# breakout.net
KiCad netlist of a schematic drawn in EAGLE
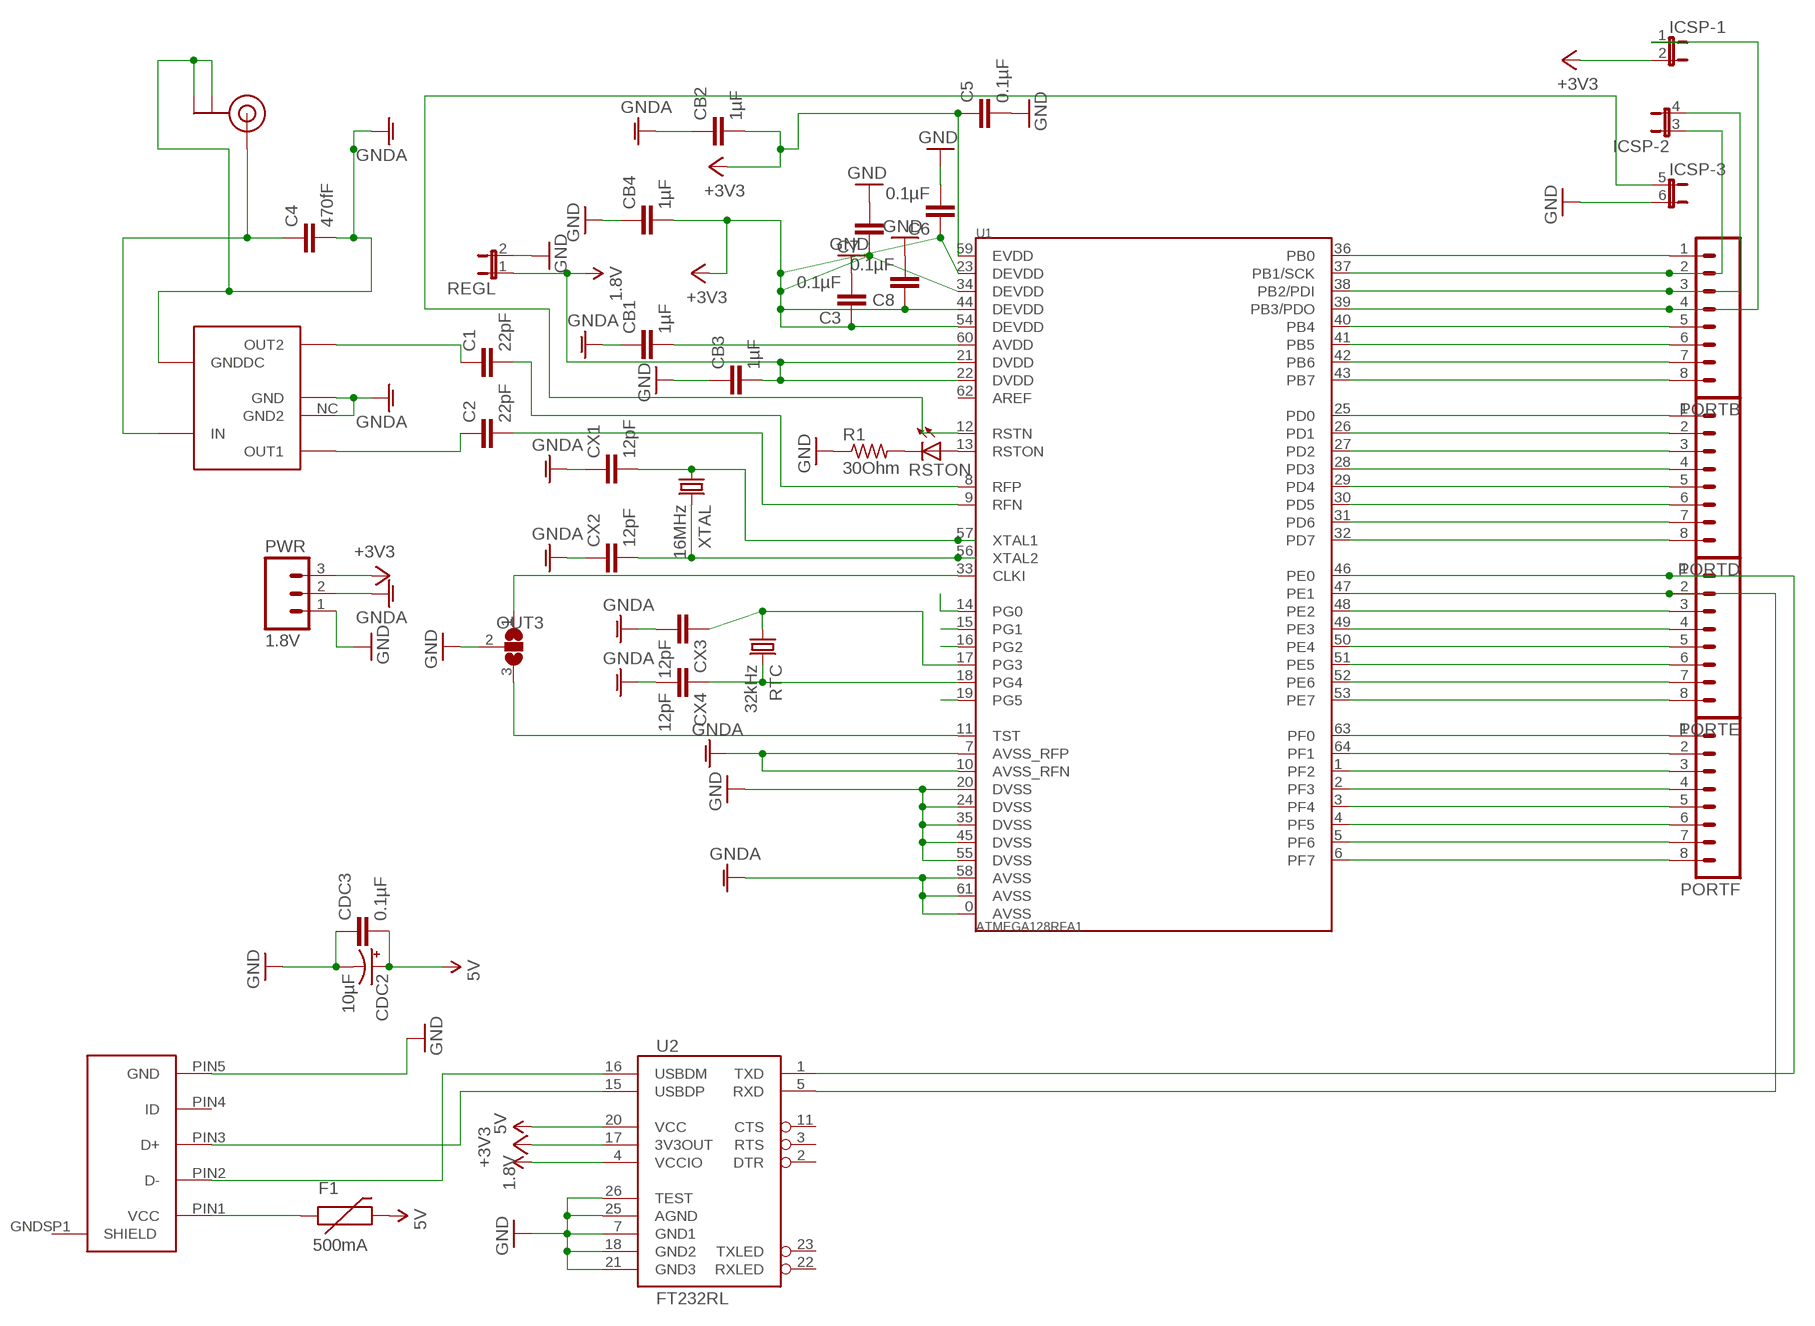
[diagram p0: schematic, sheet 1]

(export (version "E")
  (design (tool "Eeschema 10.0.6"))
  (components
    (comp (ref "B1")
      (value "2.4GHz")
      (footprint "eagle-import:WE-BAL")
      (libsource (lib "eagle-import") (part "WE-BAL"))
    )
    (comp (ref "C1")
      (value "22pF")
      (footprint "eagle-import:C0603")
      (libsource (lib "eagle-import") (part "C-EUC0603"))
    )
    (comp (ref "C2")
      (value "22pF")
      (footprint "eagle-import:C0603")
      (libsource (lib "eagle-import") (part "C-EUC0603"))
    )
    (comp (ref "C3")
      (value "0.1µF")
      (footprint "eagle-import:C0201")
      (libsource (lib "eagle-import") (part "C-EUC0201"))
    )
    (comp (ref "C4")
      (value "470fF")
      (footprint "eagle-import:C0402")
      (libsource (lib "eagle-import") (part "C-EUC0402"))
    )
    (comp (ref "C5")
      (value "0.1µF")
      (footprint "eagle-import:C0201")
      (libsource (lib "eagle-import") (part "C-EUC0201"))
    )
    (comp (ref "C6")
      (value "0.1µF")
      (footprint "eagle-import:C0201")
      (libsource (lib "eagle-import") (part "C-EUC0201"))
    )
    (comp (ref "C7")
      (value "C-EUC0201")
      (footprint "eagle-import:C0201")
      (libsource (lib "eagle-import") (part "C-EUC0201"))
    )
    (comp (ref "C8")
      (value "0.1µF")
      (footprint "eagle-import:C0201")
      (libsource (lib "eagle-import") (part "C-EUC0201"))
    )
    (comp (ref "CB1")
      (value "1µF")
      (footprint "eagle-import:C0603")
      (libsource (lib "eagle-import") (part "C-EUC0603"))
    )
    (comp (ref "CB2")
      (value "1µF")
      (footprint "eagle-import:C0603")
      (libsource (lib "eagle-import") (part "C-EUC0603"))
    )
    (comp (ref "CB3")
      (value "1µF")
      (footprint "eagle-import:C0603")
      (libsource (lib "eagle-import") (part "C-EUC0603"))
    )
    (comp (ref "CB4")
      (value "1µF")
      (footprint "eagle-import:C0603")
      (libsource (lib "eagle-import") (part "C-EUC0603"))
    )
    (comp (ref "CDC2")
      (value "10µF")
      (footprint "eagle-import:EIA3216")
      (libsource (lib "eagle-import") (part "CAP_POL1206"))
    )
    (comp (ref "CDC3")
      (value "0.1µF")
      (footprint "eagle-import:C0201")
      (libsource (lib "eagle-import") (part "C-EUC0201"))
    )
    (comp (ref "CX1")
      (value "12pF")
      (footprint "eagle-import:C0603")
      (libsource (lib "eagle-import") (part "C-EUC0603"))
    )
    (comp (ref "CX2")
      (value "12pF")
      (footprint "eagle-import:C0603")
      (libsource (lib "eagle-import") (part "C-EUC0603"))
    )
    (comp (ref "CX3")
      (value "12pF")
      (footprint "eagle-import:C0603")
      (libsource (lib "eagle-import") (part "C-EUC0603"))
    )
    (comp (ref "CX4")
      (value "12pF")
      (footprint "eagle-import:C0603")
      (libsource (lib "eagle-import") (part "C-EUC0603"))
    )
    (comp (ref "F1")
      (value "500mA")
      (footprint "eagle-import:0603")
      (libsource (lib "eagle-import") (part "PTC0603"))
    )
    (comp (ref "ICSP")
      (value "JP3QE")
      (footprint "eagle-import:JP3Q")
      (libsource (lib "eagle-import") (part "JP3QE"))
    )
    (comp (ref "JP1")
      (value "USBMICROB")
      (footprint "eagle-import:MICROB")
      (libsource (lib "eagle-import") (part "USBMICROB"))
    )
    (comp (ref "OUT3")
      (value "SOLDERJUMPERNO")
      (footprint "eagle-import:SJ_2")
      (libsource (lib "eagle-import") (part "SJ2W"))
    )
    (comp (ref "PORTB")
      (value "M081X08")
      (footprint "eagle-import:1X08")
      (libsource (lib "eagle-import") (part "M081X08"))
    )
    (comp (ref "PORTD")
      (value "M081X08")
      (footprint "eagle-import:1X08")
      (libsource (lib "eagle-import") (part "M081X08"))
    )
    (comp (ref "PORTE")
      (value "M081X08")
      (footprint "eagle-import:1X08")
      (libsource (lib "eagle-import") (part "M081X08"))
    )
    (comp (ref "PORTF")
      (value "M081X08")
      (footprint "eagle-import:1X08")
      (libsource (lib "eagle-import") (part "M081X08"))
    )
    (comp (ref "PWR")
      (value "1.8V")
      (footprint "eagle-import:1X03")
      (libsource (lib "eagle-import") (part "M03PTH"))
    )
    (comp (ref "R1")
      (value "30Ohm")
      (footprint "eagle-import:R0603")
      (libsource (lib "eagle-import") (part "R-US_R0603"))
    )
    (comp (ref "REGL")
      (value "JP1E")
      (footprint "eagle-import:JP1")
      (libsource (lib "eagle-import") (part "JP1E"))
    )
    (comp (ref "RSTON")
      (value "LEDCHIPLED_0603")
      (footprint "eagle-import:CHIPLED_0603")
      (libsource (lib "eagle-import") (part "LEDCHIPLED_0603"))
    )
    (comp (ref "RTC")
      (value "32kHz")
      (footprint "eagle-import:TC26H")
      (libsource (lib "eagle-import") (part "CRYSTALTC26H"))
    )
    (comp (ref "U$6")
      (value "U.FL")
      (footprint "eagle-import:U.FL")
      (libsource (lib "eagle-import") (part "U.FL"))
    )
    (comp (ref "U1")
      (value "ATMEGA128RFA1")
      (footprint "eagle-import:QFN-64")
      (libsource (lib "eagle-import") (part "ATMEGA128RFA1"))
    )
    (comp (ref "U2")
      (value "FT232RL")
      (footprint "eagle-import:SSOP28DB")
      (libsource (lib "eagle-import") (part "FT232RL-BASICSSOP"))
    )
    (comp (ref "XTAL")
      (value "16MHz")
      (footprint "eagle-import:HC49UP")
      (libsource (lib "eagle-import") (part "CRYSTALHC49UP"))
    )
  )
  (nets
    (net (code "1") (name "+3V3") (class "Default")
      (node (ref "C3") (pin "1") (pinfunction "1_1") (pintype "passive"))
      (node (ref "C5") (pin "1") (pinfunction "1_1") (pintype "passive"))
      (node (ref "C6") (pin "1") (pinfunction "1_1") (pintype "passive"))
      (node (ref "C7") (pin "1") (pinfunction "1_1") (pintype "passive"))
      (node (ref "C8") (pin "1") (pinfunction "1_1") (pintype "passive"))
      (node (ref "CB2") (pin "2") (pinfunction "2_2") (pintype "passive"))
      (node (ref "CB4") (pin "2") (pinfunction "2_2") (pintype "passive"))
      (node (ref "ICSP") (pin "2") (pinfunction "2_2") (pintype "passive"))
      (node (ref "PWR") (pin "3") (pinfunction "3_3") (pintype "passive"))
      (node (ref "U1") (pin "23") (pinfunction "DEVDD_23") (pintype "bidirectional"))
      (node (ref "U1") (pin "34") (pinfunction "DEVDD_34") (pintype "bidirectional"))
      (node (ref "U1") (pin "44") (pinfunction "DEVDD_44") (pintype "bidirectional"))
      (node (ref "U1") (pin "54") (pinfunction "DEVDD_54") (pintype "bidirectional"))
      (node (ref "U1") (pin "59") (pinfunction "EVDD_59") (pintype "bidirectional"))
      (node (ref "U2") (pin "17") (pinfunction "3V3OUT_17") (pintype "output"))
    )
    (net (code "2") (name "/SHIELD") (class "Default")
      (node (ref "JP1") (pin "GNDSP1") (pinfunction "SHIELD_GNDSP1") (pintype "power_in"))
    )
    (net (code "3") (name "1.8V") (class "Default")
      (node (ref "CB3") (pin "2") (pinfunction "2_2") (pintype "passive"))
      (node (ref "REGL") (pin "1") (pinfunction "1_1") (pintype "passive"))
      (node (ref "U1") (pin "21") (pinfunction "DVDD_21") (pintype "bidirectional"))
      (node (ref "U1") (pin "22") (pinfunction "DVDD_22") (pintype "bidirectional"))
      (node (ref "U2") (pin "4") (pinfunction "VCCIO_4") (pintype "power_in"))
    )
    (net (code "4") (name "5V") (class "Default")
      (node (ref "CDC2") (pin "A") (pinfunction "+_A") (pintype "passive"))
      (node (ref "CDC3") (pin "2") (pinfunction "2_2") (pintype "passive"))
      (node (ref "F1") (pin "2") (pinfunction "2_2") (pintype "bidirectional"))
      (node (ref "U2") (pin "20") (pinfunction "VCC_20") (pintype "power_in"))
    )
    (net (code "5") (name "GND") (class "Default")
      (node (ref "C3") (pin "2") (pinfunction "2_2") (pintype "passive"))
      (node (ref "C5") (pin "2") (pinfunction "2_2") (pintype "passive"))
      (node (ref "C6") (pin "2") (pinfunction "2_2") (pintype "passive"))
      (node (ref "C7") (pin "2") (pinfunction "2_2") (pintype "passive"))
      (node (ref "C8") (pin "2") (pinfunction "2_2") (pintype "passive"))
      (node (ref "CB3") (pin "1") (pinfunction "1_1") (pintype "passive"))
      (node (ref "CB4") (pin "1") (pinfunction "1_1") (pintype "passive"))
      (node (ref "CDC2") (pin "C") (pinfunction "-_C") (pintype "passive"))
      (node (ref "CDC3") (pin "1") (pinfunction "1_1") (pintype "passive"))
      (node (ref "ICSP") (pin "6") (pinfunction "2_6") (pintype "passive"))
      (node (ref "JP1") (pin "PIN5") (pinfunction "GND_PIN5") (pintype "power_in"))
      (node (ref "OUT3") (pin "2") (pinfunction "2_2") (pintype "passive"))
      (node (ref "PWR") (pin "1") (pinfunction "1_1") (pintype "passive"))
      (node (ref "R1") (pin "1") (pinfunction "1_1") (pintype "passive"))
      (node (ref "REGL") (pin "2") (pinfunction "2_2") (pintype "passive"))
      (node (ref "U1") (pin "20") (pinfunction "DVSS_20") (pintype "bidirectional"))
      (node (ref "U1") (pin "24") (pinfunction "DVSS_24") (pintype "bidirectional"))
      (node (ref "U1") (pin "35") (pinfunction "DVSS_35") (pintype "bidirectional"))
      (node (ref "U1") (pin "45") (pinfunction "DVSS_45") (pintype "bidirectional"))
      (node (ref "U1") (pin "55") (pinfunction "DVSS_55") (pintype "bidirectional"))
      (node (ref "U2") (pin "18") (pinfunction "GND2_18") (pintype "power_in"))
      (node (ref "U2") (pin "21") (pinfunction "GND3_21") (pintype "power_in"))
      (node (ref "U2") (pin "25") (pinfunction "AGND_25") (pintype "power_in"))
      (node (ref "U2") (pin "26") (pinfunction "TEST_26") (pintype "input"))
      (node (ref "U2") (pin "7") (pinfunction "GND1_7") (pintype "power_in"))
    )
    (net (code "6") (name "GNDA") (class "Default")
      (node (ref "B1") (pin "GND") (pinfunction "GND_GND") (pintype "bidirectional"))
      (node (ref "B1") (pin "GNDDC") (pinfunction "GNDDC_GNDDC") (pintype "bidirectional"))
      (node (ref "B1") (pin "NC") (pinfunction "GND2_NC") (pintype "bidirectional"))
      (node (ref "C4") (pin "2") (pinfunction "2_2") (pintype "passive"))
      (node (ref "CB1") (pin "1") (pinfunction "1_1") (pintype "passive"))
      (node (ref "CB2") (pin "1") (pinfunction "1_1") (pintype "passive"))
      (node (ref "CX1") (pin "1") (pinfunction "1_1") (pintype "passive"))
      (node (ref "CX2") (pin "1") (pinfunction "1_1") (pintype "passive"))
      (node (ref "CX3") (pin "2") (pinfunction "2_2") (pintype "passive"))
      (node (ref "CX4") (pin "2") (pinfunction "2_2") (pintype "passive"))
      (node (ref "PWR") (pin "2") (pinfunction "2_2") (pintype "passive"))
      (node (ref "U$6") (pin "P$1") (pinfunction "GND_P$1") (pintype "bidirectional"))
      (node (ref "U$6") (pin "P$2") (pinfunction "GND_P$2") (pintype "bidirectional"))
      (node (ref "U1") (pin "0") (pinfunction "AVSS_0") (pintype "bidirectional"))
      (node (ref "U1") (pin "10") (pinfunction "AVSS_RFN_10") (pintype "bidirectional"))
      (node (ref "U1") (pin "58") (pinfunction "AVSS_58") (pintype "bidirectional"))
      (node (ref "U1") (pin "61") (pinfunction "AVSS_61") (pintype "bidirectional"))
      (node (ref "U1") (pin "7") (pinfunction "AVSS_RFP_7") (pintype "bidirectional"))
    )
    (net (code "7") (name "Net-(B1-PadOUT1)") (class "Default")
      (node (ref "B1") (pin "OUT1") (pinfunction "OUT1_OUT1") (pintype "bidirectional"))
      (node (ref "C2") (pin "1") (pinfunction "1_1") (pintype "passive"))
    )
    (net (code "8") (name "Net-(B1-PadOUT2)") (class "Default")
      (node (ref "B1") (pin "OUT2") (pinfunction "OUT2_OUT2") (pintype "bidirectional"))
      (node (ref "C1") (pin "1") (pinfunction "1_1") (pintype "passive"))
    )
    (net (code "9") (name "Net-(ICSPB-1)") (class "Default")
      (node (ref "ICSP") (pin "3") (pinfunction "1_3") (pintype "passive"))
      (node (ref "PORTB") (pin "2") (pinfunction "2_2") (pintype "passive"))
      (node (ref "U1") (pin "37") (pinfunction "PB1/SCK_37") (pintype "bidirectional"))
    )
    (net (code "10") (name "Net-(ICSPB-2)") (class "Default")
      (node (ref "ICSP") (pin "4") (pinfunction "2_4") (pintype "passive"))
      (node (ref "PORTB") (pin "3") (pinfunction "3_3") (pintype "passive"))
      (node (ref "U1") (pin "38") (pinfunction "PB2/PDI_38") (pintype "bidirectional"))
    )
    (net (code "11") (name "Net-(ICSPC-1)") (class "Default")
      (node (ref "ICSP") (pin "5") (pinfunction "1_5") (pintype "passive"))
      (node (ref "U1") (pin "12") (pinfunction "RSTN_12") (pintype "bidirectional"))
    )
    (net (code "12") (name "Net-(JP1-D+)") (class "Default")
      (node (ref "JP1") (pin "PIN3") (pinfunction "D+_PIN3") (pintype "bidirectional"))
      (node (ref "U2") (pin "15") (pinfunction "USBDP_15") (pintype "bidirectional"))
    )
    (net (code "13") (name "Net-(JP1-D-)") (class "Default")
      (node (ref "JP1") (pin "PIN2") (pinfunction "D-_PIN2") (pintype "bidirectional"))
      (node (ref "U2") (pin "16") (pinfunction "USBDM_16") (pintype "bidirectional"))
    )
    (net (code "14") (name "Net-(JP1-VCC)") (class "Default")
      (node (ref "F1") (pin "1") (pinfunction "1_1") (pintype "bidirectional"))
      (node (ref "JP1") (pin "PIN1") (pinfunction "VCC_PIN1") (pintype "power_in"))
    )
    (net (code "15") (name "Net-(R1-Pad2)") (class "Default")
      (node (ref "R1") (pin "2") (pinfunction "2_2") (pintype "passive"))
      (node (ref "RSTON") (pin "C") (pinfunction "C_C") (pintype "passive"))
    )
    (net (code "16") (name "Net-(U$6-SIGNAL)") (class "Default")
      (node (ref "B1") (pin "IN") (pinfunction "IN_IN") (pintype "bidirectional"))
      (node (ref "C4") (pin "1") (pinfunction "1_1") (pintype "passive"))
      (node (ref "U$6") (pin "P$3") (pinfunction "SIGNAL_P$3") (pintype "bidirectional"))
    )
    (net (code "17") (name "Net-(U1-AVDD)") (class "Default")
      (node (ref "CB1") (pin "2") (pinfunction "2_2") (pintype "passive"))
      (node (ref "U1") (pin "60") (pinfunction "AVDD_60") (pintype "bidirectional"))
    )
    (net (code "18") (name "Net-(U1-CLKI)") (class "Default")
      (node (ref "OUT3") (pin "1") (pinfunction "1_1") (pintype "passive"))
      (node (ref "U1") (pin "33") (pinfunction "CLKI_33") (pintype "bidirectional"))
    )
    (net (code "19") (name "Net-(U1-PB0)") (class "Default")
      (node (ref "PORTB") (pin "1") (pinfunction "1_1") (pintype "passive"))
      (node (ref "U1") (pin "36") (pinfunction "PB0_36") (pintype "bidirectional"))
    )
    (net (code "20") (name "Net-(U1-PB3{slash}PDO)") (class "Default")
      (node (ref "ICSP") (pin "1") (pinfunction "1_1") (pintype "passive"))
      (node (ref "PORTB") (pin "4") (pinfunction "4_4") (pintype "passive"))
      (node (ref "U1") (pin "39") (pinfunction "PB3/PDO_39") (pintype "bidirectional"))
    )
    (net (code "21") (name "Net-(U1-PB4)") (class "Default")
      (node (ref "PORTB") (pin "5") (pinfunction "5_5") (pintype "passive"))
      (node (ref "U1") (pin "40") (pinfunction "PB4_40") (pintype "bidirectional"))
    )
    (net (code "22") (name "Net-(U1-PB5)") (class "Default")
      (node (ref "PORTB") (pin "6") (pinfunction "6_6") (pintype "passive"))
      (node (ref "U1") (pin "41") (pinfunction "PB5_41") (pintype "bidirectional"))
    )
    (net (code "23") (name "Net-(U1-PB6)") (class "Default")
      (node (ref "PORTB") (pin "7") (pinfunction "7_7") (pintype "passive"))
      (node (ref "U1") (pin "42") (pinfunction "PB6_42") (pintype "bidirectional"))
    )
    (net (code "24") (name "Net-(U1-PB7)") (class "Default")
      (node (ref "PORTB") (pin "8") (pinfunction "8_8") (pintype "passive"))
      (node (ref "U1") (pin "43") (pinfunction "PB7_43") (pintype "bidirectional"))
    )
    (net (code "25") (name "Net-(U1-PD0)") (class "Default")
      (node (ref "PORTD") (pin "1") (pinfunction "1_1") (pintype "passive"))
      (node (ref "U1") (pin "25") (pinfunction "PD0_25") (pintype "bidirectional"))
    )
    (net (code "26") (name "Net-(U1-PD1)") (class "Default")
      (node (ref "PORTD") (pin "2") (pinfunction "2_2") (pintype "passive"))
      (node (ref "U1") (pin "26") (pinfunction "PD1_26") (pintype "bidirectional"))
    )
    (net (code "27") (name "Net-(U1-PD2)") (class "Default")
      (node (ref "PORTD") (pin "3") (pinfunction "3_3") (pintype "passive"))
      (node (ref "U1") (pin "27") (pinfunction "PD2_27") (pintype "bidirectional"))
    )
    (net (code "28") (name "Net-(U1-PD3)") (class "Default")
      (node (ref "PORTD") (pin "4") (pinfunction "4_4") (pintype "passive"))
      (node (ref "U1") (pin "28") (pinfunction "PD3_28") (pintype "bidirectional"))
    )
    (net (code "29") (name "Net-(U1-PD4)") (class "Default")
      (node (ref "PORTD") (pin "5") (pinfunction "5_5") (pintype "passive"))
      (node (ref "U1") (pin "29") (pinfunction "PD4_29") (pintype "bidirectional"))
    )
    (net (code "30") (name "Net-(U1-PD5)") (class "Default")
      (node (ref "PORTD") (pin "6") (pinfunction "6_6") (pintype "passive"))
      (node (ref "U1") (pin "30") (pinfunction "PD5_30") (pintype "bidirectional"))
    )
    (net (code "31") (name "Net-(U1-PD6)") (class "Default")
      (node (ref "PORTD") (pin "7") (pinfunction "7_7") (pintype "passive"))
      (node (ref "U1") (pin "31") (pinfunction "PD6_31") (pintype "bidirectional"))
    )
    (net (code "32") (name "Net-(U1-PD7)") (class "Default")
      (node (ref "PORTD") (pin "8") (pinfunction "8_8") (pintype "passive"))
      (node (ref "U1") (pin "32") (pinfunction "PD7_32") (pintype "bidirectional"))
    )
    (net (code "33") (name "Net-(U1-PE0)") (class "Default")
      (node (ref "PORTE") (pin "1") (pinfunction "1_1") (pintype "passive"))
      (node (ref "U1") (pin "46") (pinfunction "PE0_46") (pintype "bidirectional"))
      (node (ref "U2") (pin "1") (pinfunction "TXD_1") (pintype "output"))
    )
    (net (code "34") (name "Net-(U1-PE1)") (class "Default")
      (node (ref "PORTE") (pin "2") (pinfunction "2_2") (pintype "passive"))
      (node (ref "U1") (pin "47") (pinfunction "PE1_47") (pintype "bidirectional"))
      (node (ref "U2") (pin "5") (pinfunction "RXD_5") (pintype "input"))
    )
    (net (code "35") (name "Net-(U1-PE2)") (class "Default")
      (node (ref "PORTE") (pin "3") (pinfunction "3_3") (pintype "passive"))
      (node (ref "U1") (pin "48") (pinfunction "PE2_48") (pintype "bidirectional"))
    )
    (net (code "36") (name "Net-(U1-PE3)") (class "Default")
      (node (ref "PORTE") (pin "4") (pinfunction "4_4") (pintype "passive"))
      (node (ref "U1") (pin "49") (pinfunction "PE3_49") (pintype "bidirectional"))
    )
    (net (code "37") (name "Net-(U1-PE4)") (class "Default")
      (node (ref "PORTE") (pin "5") (pinfunction "5_5") (pintype "passive"))
      (node (ref "U1") (pin "50") (pinfunction "PE4_50") (pintype "bidirectional"))
    )
    (net (code "38") (name "Net-(U1-PE5)") (class "Default")
      (node (ref "PORTE") (pin "6") (pinfunction "6_6") (pintype "passive"))
      (node (ref "U1") (pin "51") (pinfunction "PE5_51") (pintype "bidirectional"))
    )
    (net (code "39") (name "Net-(U1-PE6)") (class "Default")
      (node (ref "PORTE") (pin "7") (pinfunction "7_7") (pintype "passive"))
      (node (ref "U1") (pin "52") (pinfunction "PE6_52") (pintype "bidirectional"))
    )
    (net (code "40") (name "Net-(U1-PE7)") (class "Default")
      (node (ref "PORTE") (pin "8") (pinfunction "8_8") (pintype "passive"))
      (node (ref "U1") (pin "53") (pinfunction "PE7_53") (pintype "bidirectional"))
    )
    (net (code "41") (name "Net-(U1-PF0)") (class "Default")
      (node (ref "PORTF") (pin "1") (pinfunction "1_1") (pintype "passive"))
      (node (ref "U1") (pin "63") (pinfunction "PF0_63") (pintype "bidirectional"))
    )
    (net (code "42") (name "Net-(U1-PF1)") (class "Default")
      (node (ref "PORTF") (pin "2") (pinfunction "2_2") (pintype "passive"))
      (node (ref "U1") (pin "64") (pinfunction "PF1_64") (pintype "bidirectional"))
    )
    (net (code "43") (name "Net-(U1-PF2)") (class "Default")
      (node (ref "PORTF") (pin "3") (pinfunction "3_3") (pintype "passive"))
      (node (ref "U1") (pin "1") (pinfunction "PF2_1") (pintype "bidirectional"))
    )
    (net (code "44") (name "Net-(U1-PF3)") (class "Default")
      (node (ref "PORTF") (pin "4") (pinfunction "4_4") (pintype "passive"))
      (node (ref "U1") (pin "2") (pinfunction "PF3_2") (pintype "bidirectional"))
    )
    (net (code "45") (name "Net-(U1-PF4)") (class "Default")
      (node (ref "PORTF") (pin "5") (pinfunction "5_5") (pintype "passive"))
      (node (ref "U1") (pin "3") (pinfunction "PF4_3") (pintype "bidirectional"))
    )
    (net (code "46") (name "Net-(U1-PF5)") (class "Default")
      (node (ref "PORTF") (pin "6") (pinfunction "6_6") (pintype "passive"))
      (node (ref "U1") (pin "4") (pinfunction "PF5_4") (pintype "bidirectional"))
    )
    (net (code "47") (name "Net-(U1-PF6)") (class "Default")
      (node (ref "PORTF") (pin "7") (pinfunction "7_7") (pintype "passive"))
      (node (ref "U1") (pin "5") (pinfunction "PF6_5") (pintype "bidirectional"))
    )
    (net (code "48") (name "Net-(U1-PF7)") (class "Default")
      (node (ref "PORTF") (pin "8") (pinfunction "8_8") (pintype "passive"))
      (node (ref "U1") (pin "6") (pinfunction "PF7_6") (pintype "bidirectional"))
    )
    (net (code "49") (name "Net-(U1-PG3)") (class "Default")
      (node (ref "CX3") (pin "1") (pinfunction "1_1") (pintype "passive"))
      (node (ref "RTC") (pin "1") (pinfunction "1_1") (pintype "passive"))
      (node (ref "U1") (pin "17") (pinfunction "PG3_17") (pintype "bidirectional"))
    )
    (net (code "50") (name "Net-(U1-PG4)") (class "Default")
      (node (ref "CX4") (pin "1") (pinfunction "1_1") (pintype "passive"))
      (node (ref "RTC") (pin "2") (pinfunction "2_2") (pintype "passive"))
      (node (ref "U1") (pin "18") (pinfunction "PG4_18") (pintype "bidirectional"))
    )
    (net (code "51") (name "Net-(U1-RFN)") (class "Default")
      (node (ref "C2") (pin "2") (pinfunction "2_2") (pintype "passive"))
      (node (ref "U1") (pin "9") (pinfunction "RFN_9") (pintype "bidirectional"))
    )
    (net (code "52") (name "Net-(U1-RFP)") (class "Default")
      (node (ref "C1") (pin "2") (pinfunction "2_2") (pintype "passive"))
      (node (ref "U1") (pin "8") (pinfunction "RFP_8") (pintype "bidirectional"))
    )
    (net (code "53") (name "Net-(U1-RSTON)") (class "Default")
      (node (ref "RSTON") (pin "A") (pinfunction "A_A") (pintype "passive"))
      (node (ref "U1") (pin "13") (pinfunction "RSTON_13") (pintype "bidirectional"))
    )
    (net (code "54") (name "Net-(U1-TST)") (class "Default")
      (node (ref "OUT3") (pin "3") (pinfunction "3_3") (pintype "passive"))
      (node (ref "U1") (pin "11") (pinfunction "TST_11") (pintype "bidirectional"))
    )
    (net (code "55") (name "Net-(U1-XTAL1)") (class "Default")
      (node (ref "CX1") (pin "2") (pinfunction "2_2") (pintype "passive"))
      (node (ref "U1") (pin "57") (pinfunction "XTAL1_57") (pintype "bidirectional"))
      (node (ref "XTAL") (pin "1") (pinfunction "1_1") (pintype "passive"))
    )
    (net (code "56") (name "Net-(U1-XTAL2)") (class "Default")
      (node (ref "CX2") (pin "2") (pinfunction "2_2") (pintype "passive"))
      (node (ref "U1") (pin "56") (pinfunction "XTAL2_56") (pintype "bidirectional"))
      (node (ref "XTAL") (pin "2") (pinfunction "2_2") (pintype "passive"))
    )
    (net (code "57") (name "unconnected-(JP1-ID-PadPIN4)") (class "Default")
      (node (ref "JP1") (pin "PIN4") (pinfunction "ID_PIN4") (pintype "input"))
    )
    (net (code "58") (name "unconnected-(U1-AREF-Pad62)") (class "Default")
      (node (ref "U1") (pin "62") (pinfunction "AREF_62") (pintype "bidirectional"))
    )
    (net (code "59") (name "unconnected-(U1-PG0-Pad14)") (class "Default")
      (node (ref "U1") (pin "14") (pinfunction "PG0_14") (pintype "bidirectional"))
    )
    (net (code "60") (name "unconnected-(U1-PG1-Pad15)") (class "Default")
      (node (ref "U1") (pin "15") (pinfunction "PG1_15") (pintype "bidirectional"))
    )
    (net (code "61") (name "unconnected-(U1-PG2-Pad16)") (class "Default")
      (node (ref "U1") (pin "16") (pinfunction "PG2_16") (pintype "bidirectional"))
    )
    (net (code "62") (name "unconnected-(U1-PG5-Pad19)") (class "Default")
      (node (ref "U1") (pin "19") (pinfunction "PG5_19") (pintype "bidirectional"))
    )
    (net (code "63") (name "unconnected-(U2-CTS-Pad11)") (class "Default")
      (node (ref "U2") (pin "11") (pinfunction "CTS_11") (pintype "bidirectional"))
    )
    (net (code "64") (name "unconnected-(U2-DTR-Pad2)") (class "Default")
      (node (ref "U2") (pin "2") (pinfunction "DTR_2") (pintype "bidirectional"))
    )
    (net (code "65") (name "unconnected-(U2-RTS-Pad3)") (class "Default")
      (node (ref "U2") (pin "3") (pinfunction "RTS_3") (pintype "bidirectional"))
    )
    (net (code "66") (name "unconnected-(U2-RXLED-Pad22)") (class "Default")
      (node (ref "U2") (pin "22") (pinfunction "RXLED_22") (pintype "bidirectional"))
    )
    (net (code "67") (name "unconnected-(U2-TXLED-Pad23)") (class "Default")
      (node (ref "U2") (pin "23") (pinfunction "TXLED_23") (pintype "bidirectional"))
    )
  )
)
